# hzbcpu1.net
KiCad netlist of a schematic drawn in EAGLE
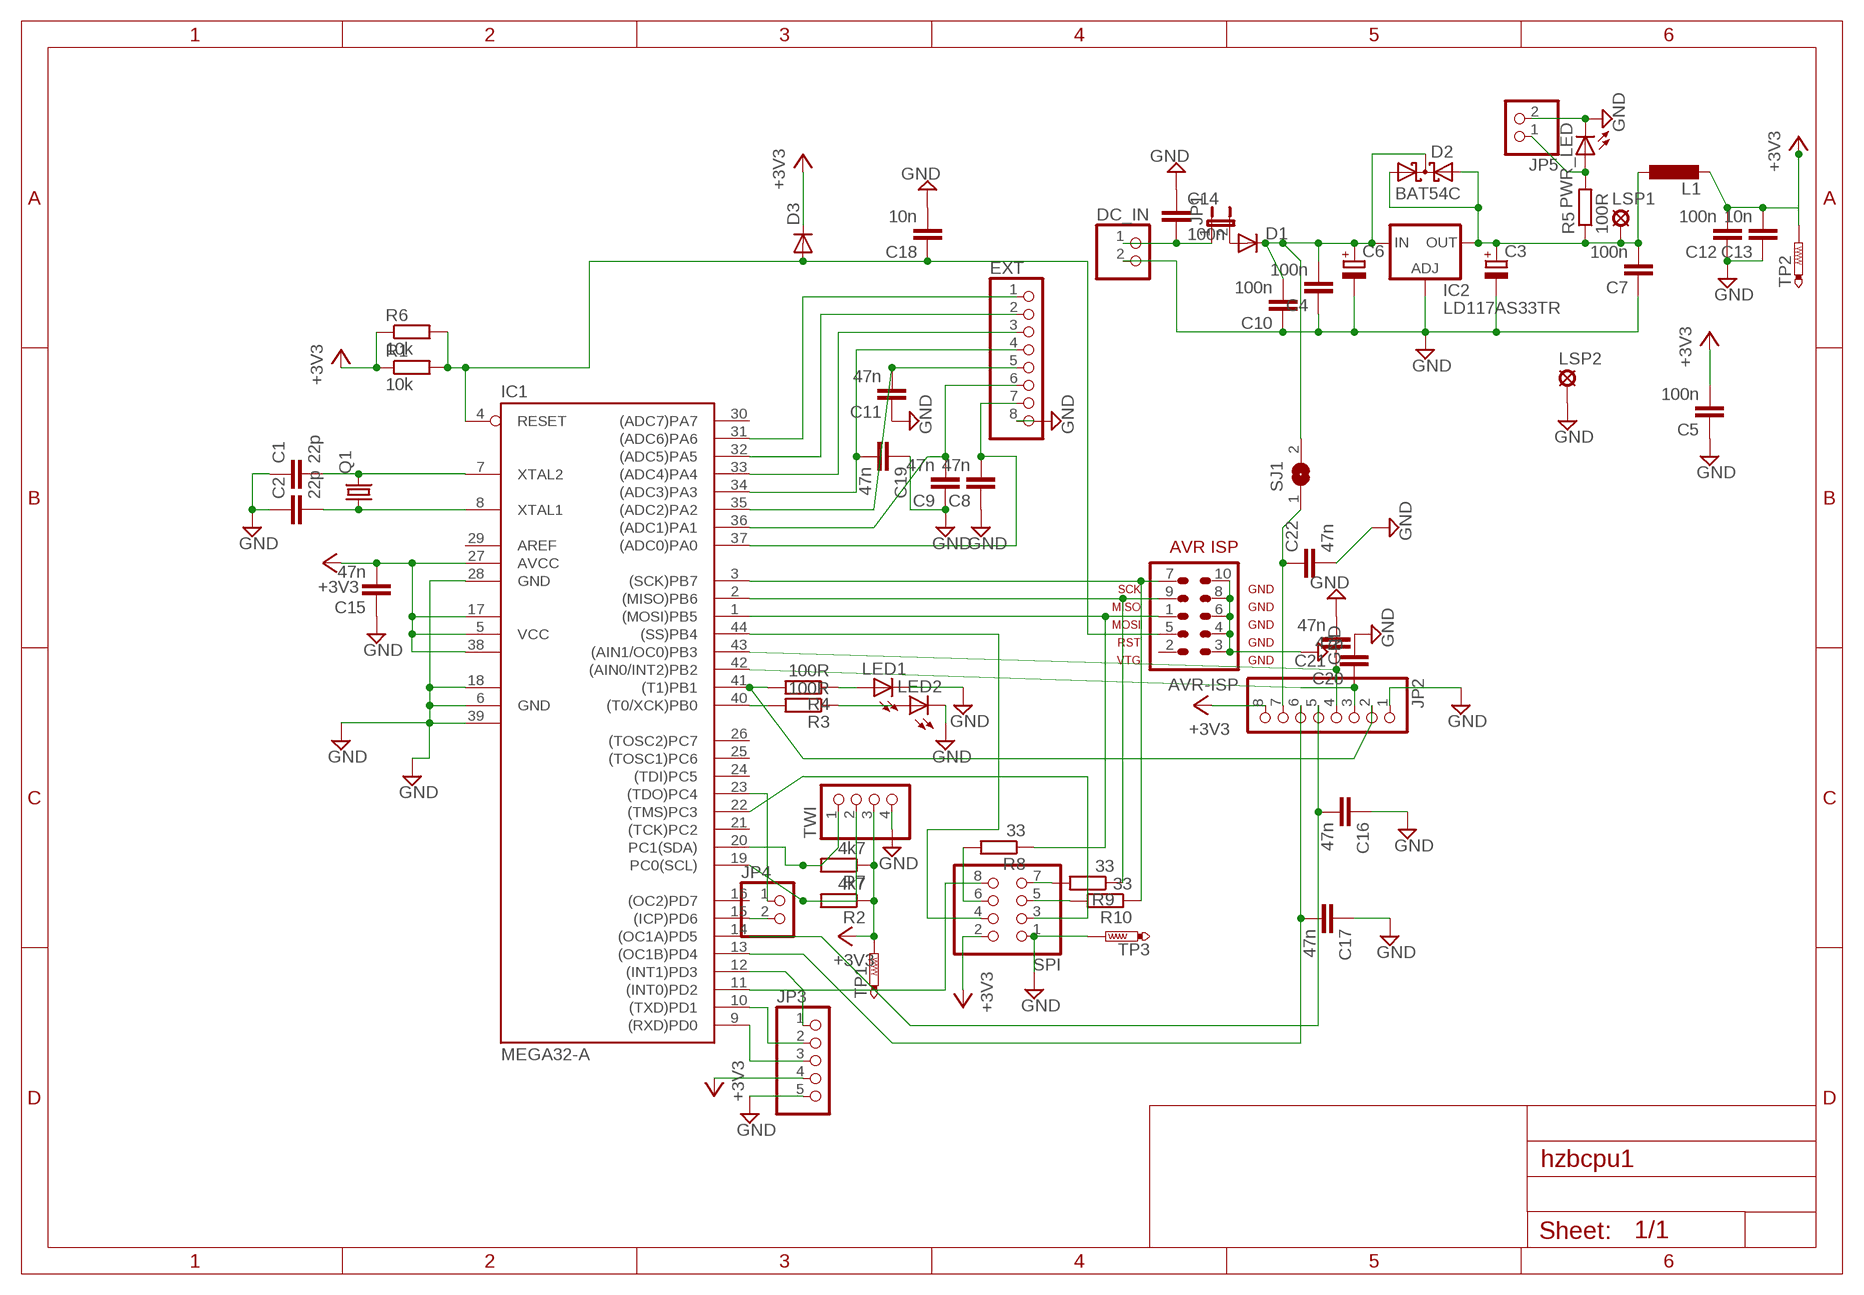
[diagram p0: schematic, sheet 1]

(export (version "E")
  (design (tool "Eeschema 10.0.6"))
  (components
    (comp (ref "AVR-ISP")
      (value "AVR-ISP-10")
      (footprint "eagle-import:AVR-ISP-10")
      (libsource (lib "eagle-import") (part "AVR-ISP-10"))
    )
    (comp (ref "C1")
      (value "22p")
      (footprint "eagle-import:C1206")
      (libsource (lib "eagle-import") (part "C-EUC1206"))
    )
    (comp (ref "C2")
      (value "22p")
      (footprint "eagle-import:C1206")
      (libsource (lib "eagle-import") (part "C-EUC1206"))
    )
    (comp (ref "C3")
      (value "CPOL-EUSMCD")
      (footprint "eagle-import:SMC_D")
      (libsource (lib "eagle-import") (part "CPOL-EUSMCD"))
    )
    (comp (ref "C4")
      (value "100n")
      (footprint "eagle-import:C1206")
      (libsource (lib "eagle-import") (part "C-EUC1206"))
    )
    (comp (ref "C5")
      (value "100n")
      (footprint "eagle-import:C0805")
      (libsource (lib "eagle-import") (part "C-EUC0805"))
    )
    (comp (ref "C6")
      (value "CPOL-EUSMCD")
      (footprint "eagle-import:SMC_D")
      (libsource (lib "eagle-import") (part "CPOL-EUSMCD"))
    )
    (comp (ref "C7")
      (value "100n")
      (footprint "eagle-import:C1206")
      (libsource (lib "eagle-import") (part "C-EUC1206"))
    )
    (comp (ref "C8")
      (value "47n")
      (footprint "eagle-import:C1206")
      (libsource (lib "eagle-import") (part "C-EUC1206"))
    )
    (comp (ref "C9")
      (value "47n")
      (footprint "eagle-import:C1206")
      (libsource (lib "eagle-import") (part "C-EUC1206"))
    )
    (comp (ref "C10")
      (value "100n")
      (footprint "eagle-import:C1206")
      (libsource (lib "eagle-import") (part "C-EUC1206"))
    )
    (comp (ref "C11")
      (value "47n")
      (footprint "eagle-import:C1206")
      (libsource (lib "eagle-import") (part "C-EUC1206"))
    )
    (comp (ref "C12")
      (value "100n")
      (footprint "eagle-import:C1206")
      (libsource (lib "eagle-import") (part "C-EUC1206"))
    )
    (comp (ref "C13")
      (value "10n")
      (footprint "eagle-import:C0805")
      (libsource (lib "eagle-import") (part "C-EUC0805"))
    )
    (comp (ref "C14")
      (value "100n")
      (footprint "eagle-import:C1206")
      (libsource (lib "eagle-import") (part "C-EUC1206"))
    )
    (comp (ref "C15")
      (value "47n")
      (footprint "eagle-import:C1206")
      (libsource (lib "eagle-import") (part "C-EUC1206"))
    )
    (comp (ref "C16")
      (value "47n")
      (footprint "eagle-import:C0805")
      (libsource (lib "eagle-import") (part "C-EUC0805"))
    )
    (comp (ref "C17")
      (value "47n")
      (footprint "eagle-import:C0805")
      (libsource (lib "eagle-import") (part "C-EUC0805"))
    )
    (comp (ref "C18")
      (value "10n")
      (footprint "eagle-import:C0805")
      (libsource (lib "eagle-import") (part "C-EUC0805"))
    )
    (comp (ref "C19")
      (value "47n")
      (footprint "eagle-import:C1206")
      (libsource (lib "eagle-import") (part "C-EUC1206"))
    )
    (comp (ref "C20")
      (value "47n")
      (footprint "eagle-import:C1206")
      (libsource (lib "eagle-import") (part "C-EUC1206"))
    )
    (comp (ref "C21")
      (value "47n")
      (footprint "eagle-import:C1206")
      (libsource (lib "eagle-import") (part "C-EUC1206"))
    )
    (comp (ref "C22")
      (value "47n")
      (footprint "eagle-import:C1206")
      (libsource (lib "eagle-import") (part "C-EUC1206"))
    )
    (comp (ref "D1")
      (value "DIODE-DO214AA")
      (footprint "eagle-import:DO214AA")
      (libsource (lib "eagle-import") (part "DIODE-DO214AA"))
    )
    (comp (ref "D2")
      (value "BAT54C")
      (footprint "eagle-import:SOT23")
      (libsource (lib "eagle-import") (part "BAT54C"))
    )
    (comp (ref "D3")
      (value "DIODE-DO214AA")
      (footprint "eagle-import:DO214AA")
      (libsource (lib "eagle-import") (part "DIODE-DO214AA"))
    )
    (comp (ref "DC_IN")
      (value "PINHD-1X2")
      (footprint "eagle-import:1X02")
      (libsource (lib "eagle-import") (part "PINHD-1X2"))
    )
    (comp (ref "EXT")
      (value "PINHD-1X8")
      (footprint "eagle-import:1X08")
      (libsource (lib "eagle-import") (part "PINHD-1X8"))
    )
    (comp (ref "IC1")
      (value "MEGA32-A")
      (footprint "eagle-import:TQFP44")
      (fields (field (name "MPN") "ATMEGA32-16AU"))
      (libsource (lib "eagle-import") (part "MEGA32-A"))
    )
    (comp (ref "IC2")
      (value "LD117AS33TR")
      (footprint "eagle-import:SOT223")
      (libsource (lib "eagle-import") (part "LD117A?S33TR"))
    )
    (comp (ref "JP1")
      (value "JP1E")
      (footprint "eagle-import:JP1")
      (libsource (lib "eagle-import") (part "JP1E"))
    )
    (comp (ref "JP2")
      (value "PINHD-1X8")
      (footprint "eagle-import:1X08")
      (libsource (lib "eagle-import") (part "PINHD-1X8"))
    )
    (comp (ref "JP3")
      (value "PINHD-1X5")
      (footprint "eagle-import:1X05")
      (libsource (lib "eagle-import") (part "PINHD-1X5"))
    )
    (comp (ref "JP4")
      (value "PINHD-1X2")
      (footprint "eagle-import:1X02")
      (libsource (lib "eagle-import") (part "PINHD-1X2"))
    )
    (comp (ref "JP5")
      (value "PINHD-1X2")
      (footprint "eagle-import:1X02")
      (libsource (lib "eagle-import") (part "PINHD-1X2"))
    )
    (comp (ref "L1")
      (value "L-EUL3225M")
      (footprint "eagle-import:L3225M")
      (libsource (lib "eagle-import") (part "L-EUL3225M"))
    )
    (comp (ref "LED1")
      (value "LED3MM")
      (footprint "eagle-import:LED3MM")
      (libsource (lib "eagle-import") (part "LED3MM"))
    )
    (comp (ref "LED2")
      (value "LED3MM")
      (footprint "eagle-import:LED3MM")
      (libsource (lib "eagle-import") (part "LED3MM"))
    )
    (comp (ref "LSP1")
      (value "LSP11")
      (footprint "eagle-import:LSP11")
      (libsource (lib "eagle-import") (part "LSP11"))
    )
    (comp (ref "LSP2")
      (value "LSP11")
      (footprint "eagle-import:LSP11")
      (libsource (lib "eagle-import") (part "LSP11"))
    )
    (comp (ref "PWR_LED")
      (value "LED3MM")
      (footprint "eagle-import:LED3MM")
      (libsource (lib "eagle-import") (part "LED3MM"))
    )
    (comp (ref "Q1")
      (value "CRYSTALHC49UP")
      (footprint "eagle-import:HC49UP")
      (libsource (lib "eagle-import") (part "CRYSTALHC49UP"))
    )
    (comp (ref "R1")
      (value "10k")
      (footprint "eagle-import:0204_7")
      (libsource (lib "eagle-import") (part "R-EU_0204/7"))
    )
    (comp (ref "R2")
      (value "4k7")
      (footprint "eagle-import:R1206")
      (libsource (lib "eagle-import") (part "R-EU_R1206"))
    )
    (comp (ref "R3")
      (value "100R")
      (footprint "eagle-import:R1206")
      (libsource (lib "eagle-import") (part "R-EU_R1206"))
    )
    (comp (ref "R4")
      (value "100R")
      (footprint "eagle-import:R1206")
      (libsource (lib "eagle-import") (part "R-EU_R1206"))
    )
    (comp (ref "R5")
      (value "100R")
      (footprint "eagle-import:R1206")
      (libsource (lib "eagle-import") (part "R-EU_R1206"))
    )
    (comp (ref "R6")
      (value "10k")
      (footprint "eagle-import:R1206")
      (libsource (lib "eagle-import") (part "R-EU_R1206"))
    )
    (comp (ref "R7")
      (value "4k7")
      (footprint "eagle-import:R1206")
      (libsource (lib "eagle-import") (part "R-EU_R1206"))
    )
    (comp (ref "R8")
      (value "33")
      (footprint "eagle-import:R0805")
      (libsource (lib "eagle-import") (part "R-EU_R0805"))
    )
    (comp (ref "R9")
      (value "33")
      (footprint "eagle-import:R0805")
      (libsource (lib "eagle-import") (part "R-EU_R0805"))
    )
    (comp (ref "R10")
      (value "33")
      (footprint "eagle-import:R1206")
      (libsource (lib "eagle-import") (part "R-EU_R1206"))
    )
    (comp (ref "SJ1") (value "SJ") (footprint "eagle-import:SJ") (libsource (lib "eagle-import") (part "SJ")))
    (comp (ref "SPI")
      (value "PINHD-2X4")
      (footprint "eagle-import:2X04")
      (libsource (lib "eagle-import") (part "PINHD-2X4"))
    )
    (comp (ref "TP1")
      (value "PTR1B1,27")
      (footprint "eagle-import:B1,27")
      (libsource (lib "eagle-import") (part "PTR1B1,27"))
    )
    (comp (ref "TP2")
      (value "PTR1B1,27")
      (footprint "eagle-import:B1,27")
      (libsource (lib "eagle-import") (part "PTR1B1,27"))
    )
    (comp (ref "TP3")
      (value "PTR1B1,27")
      (footprint "eagle-import:B1,27")
      (libsource (lib "eagle-import") (part "PTR1B1,27"))
    )
    (comp (ref "TWI")
      (value "PINHD-1X4")
      (footprint "eagle-import:1X04")
      (libsource (lib "eagle-import") (part "PINHD-1X4"))
    )
  )
  (nets
    (net (code "1") (name "+3V3") (class "Default")
      (node (ref "C12") (pin "2") (pinfunction "2_2") (pintype "passive"))
      (node (ref "C13") (pin "2") (pinfunction "2_2") (pintype "passive"))
      (node (ref "C15") (pin "2") (pinfunction "2_2") (pintype "passive"))
      (node (ref "C5") (pin "2") (pinfunction "2_2") (pintype "passive"))
      (node (ref "D3") (pin "C") (pinfunction "C_C") (pintype "passive"))
      (node (ref "IC1") (pin "17") (pinfunction "VCC1_17") (pintype "power_in"))
      (node (ref "IC1") (pin "27") (pinfunction "AVCC_27") (pintype "power_in"))
      (node (ref "IC1") (pin "38") (pinfunction "VCC2_38") (pintype "power_in"))
      (node (ref "IC1") (pin "5") (pinfunction "VCC_5") (pintype "power_in"))
      (node (ref "JP2") (pin "8") (pinfunction "8_8") (pintype "passive"))
      (node (ref "JP3") (pin "4") (pinfunction "4_4") (pintype "passive"))
      (node (ref "L1") (pin "2") (pinfunction "2_2") (pintype "passive"))
      (node (ref "R1") (pin "1") (pinfunction "1_1") (pintype "passive"))
      (node (ref "R2") (pin "1") (pinfunction "1_1") (pintype "passive"))
      (node (ref "R6") (pin "1") (pinfunction "1_1") (pintype "passive"))
      (node (ref "R7") (pin "1") (pinfunction "1_1") (pintype "passive"))
      (node (ref "SPI") (pin "2") (pinfunction "2_2") (pintype "passive"))
      (node (ref "TP1") (pin "TP") (pinfunction "TP_TP") (pintype "input"))
      (node (ref "TP2") (pin "TP") (pinfunction "TP_TP") (pintype "input"))
      (node (ref "TWI") (pin "3") (pinfunction "3_3") (pintype "passive"))
    )
    (net (code "2") (name "GND") (class "Default")
      (node (ref "AVR-ISP") (pin "10") (pinfunction "10_10") (pintype "passive"))
      (node (ref "AVR-ISP") (pin "3") (pinfunction "3_3") (pintype "passive"))
      (node (ref "AVR-ISP") (pin "4") (pinfunction "4_4") (pintype "passive"))
      (node (ref "AVR-ISP") (pin "6") (pinfunction "6_6") (pintype "passive"))
      (node (ref "AVR-ISP") (pin "8") (pinfunction "8_8") (pintype "passive"))
      (node (ref "C1") (pin "1") (pinfunction "1_1") (pintype "passive"))
      (node (ref "C10") (pin "1") (pinfunction "1_1") (pintype "passive"))
      (node (ref "C11") (pin "1") (pinfunction "1_1") (pintype "passive"))
      (node (ref "C12") (pin "1") (pinfunction "1_1") (pintype "passive"))
      (node (ref "C13") (pin "1") (pinfunction "1_1") (pintype "passive"))
      (node (ref "C14") (pin "1") (pinfunction "1_1") (pintype "passive"))
      (node (ref "C15") (pin "1") (pinfunction "1_1") (pintype "passive"))
      (node (ref "C16") (pin "1") (pinfunction "1_1") (pintype "passive"))
      (node (ref "C17") (pin "1") (pinfunction "1_1") (pintype "passive"))
      (node (ref "C18") (pin "2") (pinfunction "2_2") (pintype "passive"))
      (node (ref "C19") (pin "1") (pinfunction "1_1") (pintype "passive"))
      (node (ref "C2") (pin "1") (pinfunction "1_1") (pintype "passive"))
      (node (ref "C20") (pin "2") (pinfunction "2_2") (pintype "passive"))
      (node (ref "C21") (pin "2") (pinfunction "2_2") (pintype "passive"))
      (node (ref "C22") (pin "2") (pinfunction "2_2") (pintype "passive"))
      (node (ref "C3") (pin "-") (pinfunction "-_-") (pintype "passive"))
      (node (ref "C4") (pin "1") (pinfunction "1_1") (pintype "passive"))
      (node (ref "C5") (pin "1") (pinfunction "1_1") (pintype "passive"))
      (node (ref "C6") (pin "-") (pinfunction "-_-") (pintype "passive"))
      (node (ref "C7") (pin "1") (pinfunction "1_1") (pintype "passive"))
      (node (ref "C8") (pin "1") (pinfunction "1_1") (pintype "passive"))
      (node (ref "C9") (pin "1") (pinfunction "1_1") (pintype "passive"))
      (node (ref "DC_IN") (pin "2") (pinfunction "2_2") (pintype "passive"))
      (node (ref "EXT") (pin "8") (pinfunction "8_8") (pintype "passive"))
      (node (ref "IC1") (pin "18") (pinfunction "GND1_18") (pintype "power_in"))
      (node (ref "IC1") (pin "28") (pinfunction "GND_28") (pintype "power_in"))
      (node (ref "IC1") (pin "39") (pinfunction "GND2_39") (pintype "power_in"))
      (node (ref "IC1") (pin "6") (pinfunction "GND_6") (pintype "power_in"))
      (node (ref "IC2") (pin "1") (pinfunction "ADJ_1") (pintype "input"))
      (node (ref "JP2") (pin "1") (pinfunction "1_1") (pintype "passive"))
      (node (ref "JP3") (pin "5") (pinfunction "5_5") (pintype "passive"))
      (node (ref "JP5") (pin "2") (pinfunction "2_2") (pintype "passive"))
      (node (ref "LED1") (pin "K") (pinfunction "C_K") (pintype "passive"))
      (node (ref "LED2") (pin "K") (pinfunction "C_K") (pintype "passive"))
      (node (ref "LSP2") (pin "MP") (pinfunction "MP_MP") (pintype "passive"))
      (node (ref "PWR_LED") (pin "K") (pinfunction "C_K") (pintype "passive"))
      (node (ref "SPI") (pin "1") (pinfunction "1_1") (pintype "passive"))
      (node (ref "TP3") (pin "TP") (pinfunction "TP_TP") (pintype "input"))
      (node (ref "TWI") (pin "4") (pinfunction "4_4") (pintype "passive"))
    )
    (net (code "3") (name "Net-(C14-Pad2)") (class "Default")
      (node (ref "C14") (pin "2") (pinfunction "2_2") (pintype "passive"))
      (node (ref "DC_IN") (pin "1") (pinfunction "1_1") (pintype "passive"))
      (node (ref "JP1") (pin "1") (pinfunction "1_1") (pintype "passive"))
    )
    (net (code "4") (name "Net-(C22-Pad1)") (class "Default")
      (node (ref "C22") (pin "1") (pinfunction "1_1") (pintype "passive"))
      (node (ref "JP2") (pin "7") (pinfunction "7_7") (pintype "passive"))
      (node (ref "SJ1") (pin "1") (pinfunction "1_1") (pintype "passive"))
    )
    (net (code "5") (name "Net-(D1-PadA)") (class "Default")
      (node (ref "D1") (pin "A") (pinfunction "A_A") (pintype "passive"))
      (node (ref "JP1") (pin "2") (pinfunction "2_2") (pintype "passive"))
    )
    (net (code "6") (name "Net-(D2-A1)") (class "Default")
      (node (ref "C3") (pin "+") (pinfunction "+_+") (pintype "passive"))
      (node (ref "C7") (pin "2") (pinfunction "2_2") (pintype "passive"))
      (node (ref "D2") (pin "1") (pinfunction "A1_1") (pintype "passive"))
      (node (ref "D2") (pin "2") (pinfunction "A2_2") (pintype "passive"))
      (node (ref "IC2") (pin "4") (pinfunction "OUT_4") (pintype "passive"))
      (node (ref "L1") (pin "1") (pinfunction "1_1") (pintype "passive"))
      (node (ref "LSP1") (pin "MP") (pinfunction "MP_MP") (pintype "passive"))
      (node (ref "R5") (pin "1") (pinfunction "1_1") (pintype "passive"))
    )
    (net (code "7") (name "Net-(D2-CC)") (class "Default")
      (node (ref "C10") (pin "2") (pinfunction "2_2") (pintype "passive"))
      (node (ref "C4") (pin "2") (pinfunction "2_2") (pintype "passive"))
      (node (ref "C6") (pin "+") (pinfunction "+_+") (pintype "passive"))
      (node (ref "D1") (pin "C") (pinfunction "C_C") (pintype "passive"))
      (node (ref "D2") (pin "3") (pinfunction "CC_3") (pintype "passive"))
      (node (ref "IC2") (pin "3") (pinfunction "IN_3") (pintype "input"))
      (node (ref "SJ1") (pin "2") (pinfunction "2_2") (pintype "passive"))
    )
    (net (code "8") (name "Net-(IC1-(ADC0)PA0)") (class "Default")
      (node (ref "C8") (pin "2") (pinfunction "2_2") (pintype "passive"))
      (node (ref "EXT") (pin "7") (pinfunction "7_7") (pintype "passive"))
      (node (ref "IC1") (pin "37") (pinfunction "(ADC0)PA0_37") (pintype "bidirectional"))
    )
    (net (code "9") (name "Net-(IC1-(ADC1)PA1)") (class "Default")
      (node (ref "C9") (pin "2") (pinfunction "2_2") (pintype "passive"))
      (node (ref "EXT") (pin "6") (pinfunction "6_6") (pintype "passive"))
      (node (ref "IC1") (pin "36") (pinfunction "(ADC1)PA1_36") (pintype "bidirectional"))
    )
    (net (code "10") (name "Net-(IC1-(ADC2)PA2)") (class "Default")
      (node (ref "C11") (pin "2") (pinfunction "2_2") (pintype "passive"))
      (node (ref "EXT") (pin "5") (pinfunction "5_5") (pintype "passive"))
      (node (ref "IC1") (pin "35") (pinfunction "(ADC2)PA2_35") (pintype "bidirectional"))
    )
    (net (code "11") (name "Net-(IC1-(ADC3)PA3)") (class "Default")
      (node (ref "C19") (pin "2") (pinfunction "2_2") (pintype "passive"))
      (node (ref "EXT") (pin "4") (pinfunction "4_4") (pintype "passive"))
      (node (ref "IC1") (pin "34") (pinfunction "(ADC3)PA3_34") (pintype "bidirectional"))
    )
    (net (code "12") (name "Net-(IC1-(ADC4)PA4)") (class "Default")
      (node (ref "EXT") (pin "3") (pinfunction "3_3") (pintype "passive"))
      (node (ref "IC1") (pin "33") (pinfunction "(ADC4)PA4_33") (pintype "bidirectional"))
    )
    (net (code "13") (name "Net-(IC1-(ADC5)PA5)") (class "Default")
      (node (ref "EXT") (pin "2") (pinfunction "2_2") (pintype "passive"))
      (node (ref "IC1") (pin "32") (pinfunction "(ADC5)PA5_32") (pintype "bidirectional"))
    )
    (net (code "14") (name "Net-(IC1-(ADC6)PA6)") (class "Default")
      (node (ref "EXT") (pin "1") (pinfunction "1_1") (pintype "passive"))
      (node (ref "IC1") (pin "31") (pinfunction "(ADC6)PA6_31") (pintype "bidirectional"))
    )
    (net (code "15") (name "Net-(IC1-(AIN0{slash}INT2)PB2)") (class "Default")
      (node (ref "C20") (pin "1") (pinfunction "1_1") (pintype "passive"))
      (node (ref "IC1") (pin "42") (pinfunction "(AIN0/INT2)PB2_42") (pintype "bidirectional"))
      (node (ref "JP2") (pin "3") (pinfunction "3_3") (pintype "passive"))
    )
    (net (code "16") (name "Net-(IC1-(AIN1{slash}OC0)PB3)") (class "Default")
      (node (ref "C21") (pin "1") (pinfunction "1_1") (pintype "passive"))
      (node (ref "IC1") (pin "43") (pinfunction "(AIN1/OC0)PB3_43") (pintype "bidirectional"))
      (node (ref "JP2") (pin "4") (pinfunction "4_4") (pintype "passive"))
    )
    (net (code "17") (name "Net-(IC1-(ICP)PD6)") (class "Default")
      (node (ref "IC1") (pin "15") (pinfunction "(ICP)PD6_15") (pintype "bidirectional"))
      (node (ref "JP4") (pin "2") (pinfunction "2_2") (pintype "passive"))
    )
    (net (code "18") (name "Net-(IC1-(INT0)PD2)") (class "Default")
      (node (ref "IC1") (pin "11") (pinfunction "(INT0)PD2_11") (pintype "bidirectional"))
      (node (ref "SPI") (pin "8") (pinfunction "8_8") (pintype "passive"))
    )
    (net (code "19") (name "Net-(IC1-(INT1)PD3)") (class "Default")
      (node (ref "IC1") (pin "12") (pinfunction "(INT1)PD3_12") (pintype "bidirectional"))
      (node (ref "JP3") (pin "1") (pinfunction "1_1") (pintype "passive"))
    )
    (net (code "20") (name "Net-(IC1-(MISO)PB6)") (class "Default")
      (node (ref "AVR-ISP") (pin "9") (pinfunction "9_9") (pintype "passive"))
      (node (ref "IC1") (pin "2") (pinfunction "(MISO)PB6_2") (pintype "bidirectional"))
      (node (ref "R9") (pin "1") (pinfunction "1_1") (pintype "passive"))
    )
    (net (code "21") (name "Net-(IC1-(MOSI)PB5)") (class "Default")
      (node (ref "AVR-ISP") (pin "1") (pinfunction "1_1") (pintype "passive"))
      (node (ref "IC1") (pin "1") (pinfunction "(MOSI)PB5_1") (pintype "bidirectional"))
      (node (ref "R8") (pin "1") (pinfunction "1_1") (pintype "passive"))
    )
    (net (code "22") (name "Net-(IC1-(OC1A)PD5)") (class "Default")
      (node (ref "C16") (pin "2") (pinfunction "2_2") (pintype "passive"))
      (node (ref "IC1") (pin "14") (pinfunction "(OC1A)PD5_14") (pintype "bidirectional"))
      (node (ref "JP2") (pin "5") (pinfunction "5_5") (pintype "passive"))
    )
    (net (code "23") (name "Net-(IC1-(OC1B)PD4)") (class "Default")
      (node (ref "C17") (pin "2") (pinfunction "2_2") (pintype "passive"))
      (node (ref "IC1") (pin "13") (pinfunction "(OC1B)PD4_13") (pintype "bidirectional"))
      (node (ref "JP2") (pin "6") (pinfunction "6_6") (pintype "passive"))
    )
    (net (code "24") (name "Net-(IC1-(RXD)PD0)") (class "Default")
      (node (ref "IC1") (pin "9") (pinfunction "(RXD)PD0_9") (pintype "bidirectional"))
      (node (ref "JP3") (pin "3") (pinfunction "3_3") (pintype "passive"))
    )
    (net (code "25") (name "Net-(IC1-(SCK)PB7)") (class "Default")
      (node (ref "AVR-ISP") (pin "7") (pinfunction "7_7") (pintype "passive"))
      (node (ref "IC1") (pin "3") (pinfunction "(SCK)PB7_3") (pintype "bidirectional"))
      (node (ref "R10") (pin "1") (pinfunction "1_1") (pintype "passive"))
    )
    (net (code "26") (name "Net-(IC1-(SS)PB4)") (class "Default")
      (node (ref "IC1") (pin "44") (pinfunction "(SS)PB4_44") (pintype "bidirectional"))
      (node (ref "SPI") (pin "4") (pinfunction "4_4") (pintype "passive"))
    )
    (net (code "27") (name "Net-(IC1-(T0{slash}XCK)PB0)") (class "Default")
      (node (ref "IC1") (pin "40") (pinfunction "(T0/XCK)PB0_40") (pintype "bidirectional"))
      (node (ref "R3") (pin "2") (pinfunction "2_2") (pintype "passive"))
    )
    (net (code "28") (name "Net-(IC1-(T1)PB1)") (class "Default")
      (node (ref "IC1") (pin "41") (pinfunction "(T1)PB1_41") (pintype "bidirectional"))
      (node (ref "JP2") (pin "2") (pinfunction "2_2") (pintype "passive"))
      (node (ref "R4") (pin "2") (pinfunction "2_2") (pintype "passive"))
    )
    (net (code "29") (name "Net-(IC1-(TDO)PC4)") (class "Default")
      (node (ref "IC1") (pin "23") (pinfunction "(TDO)PC4_23") (pintype "bidirectional"))
      (node (ref "JP4") (pin "1") (pinfunction "1_1") (pintype "passive"))
    )
    (net (code "30") (name "Net-(IC1-(TMS)PC3)") (class "Default")
      (node (ref "IC1") (pin "22") (pinfunction "(TMS)PC3_22") (pintype "bidirectional"))
      (node (ref "SPI") (pin "3") (pinfunction "3_3") (pintype "passive"))
    )
    (net (code "31") (name "Net-(IC1-(TXD)PD1)") (class "Default")
      (node (ref "IC1") (pin "10") (pinfunction "(TXD)PD1_10") (pintype "bidirectional"))
      (node (ref "JP3") (pin "2") (pinfunction "2_2") (pintype "passive"))
    )
    (net (code "32") (name "Net-(IC1-PC0(SCL))") (class "Default")
      (node (ref "IC1") (pin "19") (pinfunction "PC0(SCL)_19") (pintype "bidirectional"))
      (node (ref "R2") (pin "2") (pinfunction "2_2") (pintype "passive"))
      (node (ref "TWI") (pin "2") (pinfunction "2_2") (pintype "passive"))
    )
    (net (code "33") (name "Net-(IC1-PC1(SDA))") (class "Default")
      (node (ref "IC1") (pin "20") (pinfunction "PC1(SDA)_20") (pintype "bidirectional"))
      (node (ref "R7") (pin "2") (pinfunction "2_2") (pintype "passive"))
      (node (ref "TWI") (pin "1") (pinfunction "1_1") (pintype "passive"))
    )
    (net (code "34") (name "Net-(IC1-RESET)") (class "Default")
      (node (ref "AVR-ISP") (pin "5") (pinfunction "5_5") (pintype "passive"))
      (node (ref "C18") (pin "1") (pinfunction "1_1") (pintype "passive"))
      (node (ref "D3") (pin "A") (pinfunction "A_A") (pintype "passive"))
      (node (ref "IC1") (pin "4") (pinfunction "RESET_4") (pintype "input"))
      (node (ref "R1") (pin "2") (pinfunction "2_2") (pintype "passive"))
      (node (ref "R6") (pin "2") (pinfunction "2_2") (pintype "passive"))
    )
    (net (code "35") (name "Net-(IC1-XTAL1)") (class "Default")
      (node (ref "C2") (pin "2") (pinfunction "2_2") (pintype "passive"))
      (node (ref "IC1") (pin "8") (pinfunction "XTAL1_8") (pintype "bidirectional"))
      (node (ref "Q1") (pin "1") (pinfunction "1_1") (pintype "passive"))
    )
    (net (code "36") (name "Net-(IC1-XTAL2)") (class "Default")
      (node (ref "C1") (pin "2") (pinfunction "2_2") (pintype "passive"))
      (node (ref "IC1") (pin "7") (pinfunction "XTAL2_7") (pintype "bidirectional"))
      (node (ref "Q1") (pin "2") (pinfunction "2_2") (pintype "passive"))
    )
    (net (code "37") (name "Net-(JP5-Pad1)") (class "Default")
      (node (ref "JP5") (pin "1") (pinfunction "1_1") (pintype "passive"))
      (node (ref "PWR_LED") (pin "A") (pinfunction "A_A") (pintype "passive"))
      (node (ref "R5") (pin "2") (pinfunction "2_2") (pintype "passive"))
    )
    (net (code "38") (name "Net-(LED1-PadA)") (class "Default")
      (node (ref "LED1") (pin "A") (pinfunction "A_A") (pintype "passive"))
      (node (ref "R4") (pin "1") (pinfunction "1_1") (pintype "passive"))
    )
    (net (code "39") (name "Net-(LED2-PadA)") (class "Default")
      (node (ref "LED2") (pin "A") (pinfunction "A_A") (pintype "passive"))
      (node (ref "R3") (pin "1") (pinfunction "1_1") (pintype "passive"))
    )
    (net (code "40") (name "Net-(R8-Pad2)") (class "Default")
      (node (ref "R8") (pin "2") (pinfunction "2_2") (pintype "passive"))
      (node (ref "SPI") (pin "6") (pinfunction "6_6") (pintype "passive"))
    )
    (net (code "41") (name "Net-(R9-Pad2)") (class "Default")
      (node (ref "R9") (pin "2") (pinfunction "2_2") (pintype "passive"))
      (node (ref "SPI") (pin "7") (pinfunction "7_7") (pintype "passive"))
    )
    (net (code "42") (name "Net-(R10-Pad2)") (class "Default")
      (node (ref "R10") (pin "2") (pinfunction "2_2") (pintype "passive"))
      (node (ref "SPI") (pin "5") (pinfunction "5_5") (pintype "passive"))
    )
    (net (code "43") (name "unconnected-(AVR-ISP-Pad2)") (class "Default")
      (node (ref "AVR-ISP") (pin "2") (pinfunction "2_2") (pintype "passive"))
    )
    (net (code "44") (name "unconnected-(IC1-(ADC7)PA7-Pad30)") (class "Default")
      (node (ref "IC1") (pin "30") (pinfunction "(ADC7)PA7_30") (pintype "bidirectional"))
    )
    (net (code "45") (name "unconnected-(IC1-(OC2)PD7-Pad16)") (class "Default")
      (node (ref "IC1") (pin "16") (pinfunction "(OC2)PD7_16") (pintype "bidirectional"))
    )
    (net (code "46") (name "unconnected-(IC1-(TCK)PC2-Pad21)") (class "Default")
      (node (ref "IC1") (pin "21") (pinfunction "(TCK)PC2_21") (pintype "bidirectional"))
    )
    (net (code "47") (name "unconnected-(IC1-(TDI)PC5-Pad24)") (class "Default")
      (node (ref "IC1") (pin "24") (pinfunction "(TDI)PC5_24") (pintype "bidirectional"))
    )
    (net (code "48") (name "unconnected-(IC1-(TOSC1)PC6-Pad25)") (class "Default")
      (node (ref "IC1") (pin "25") (pinfunction "(TOSC1)PC6_25") (pintype "bidirectional"))
    )
    (net (code "49") (name "unconnected-(IC1-(TOSC2)PC7-Pad26)") (class "Default")
      (node (ref "IC1") (pin "26") (pinfunction "(TOSC2)PC7_26") (pintype "bidirectional"))
    )
    (net (code "50") (name "unconnected-(IC1-AREF-Pad29)") (class "Default")
      (node (ref "IC1") (pin "29") (pinfunction "AREF_29") (pintype "passive"))
    )
  )
)
